# Pure_VCO_SMD_V2_2_d4f9a5cf-5e05-4fe2-98c.net
KiCad netlist of a schematic drawn in EAGLE
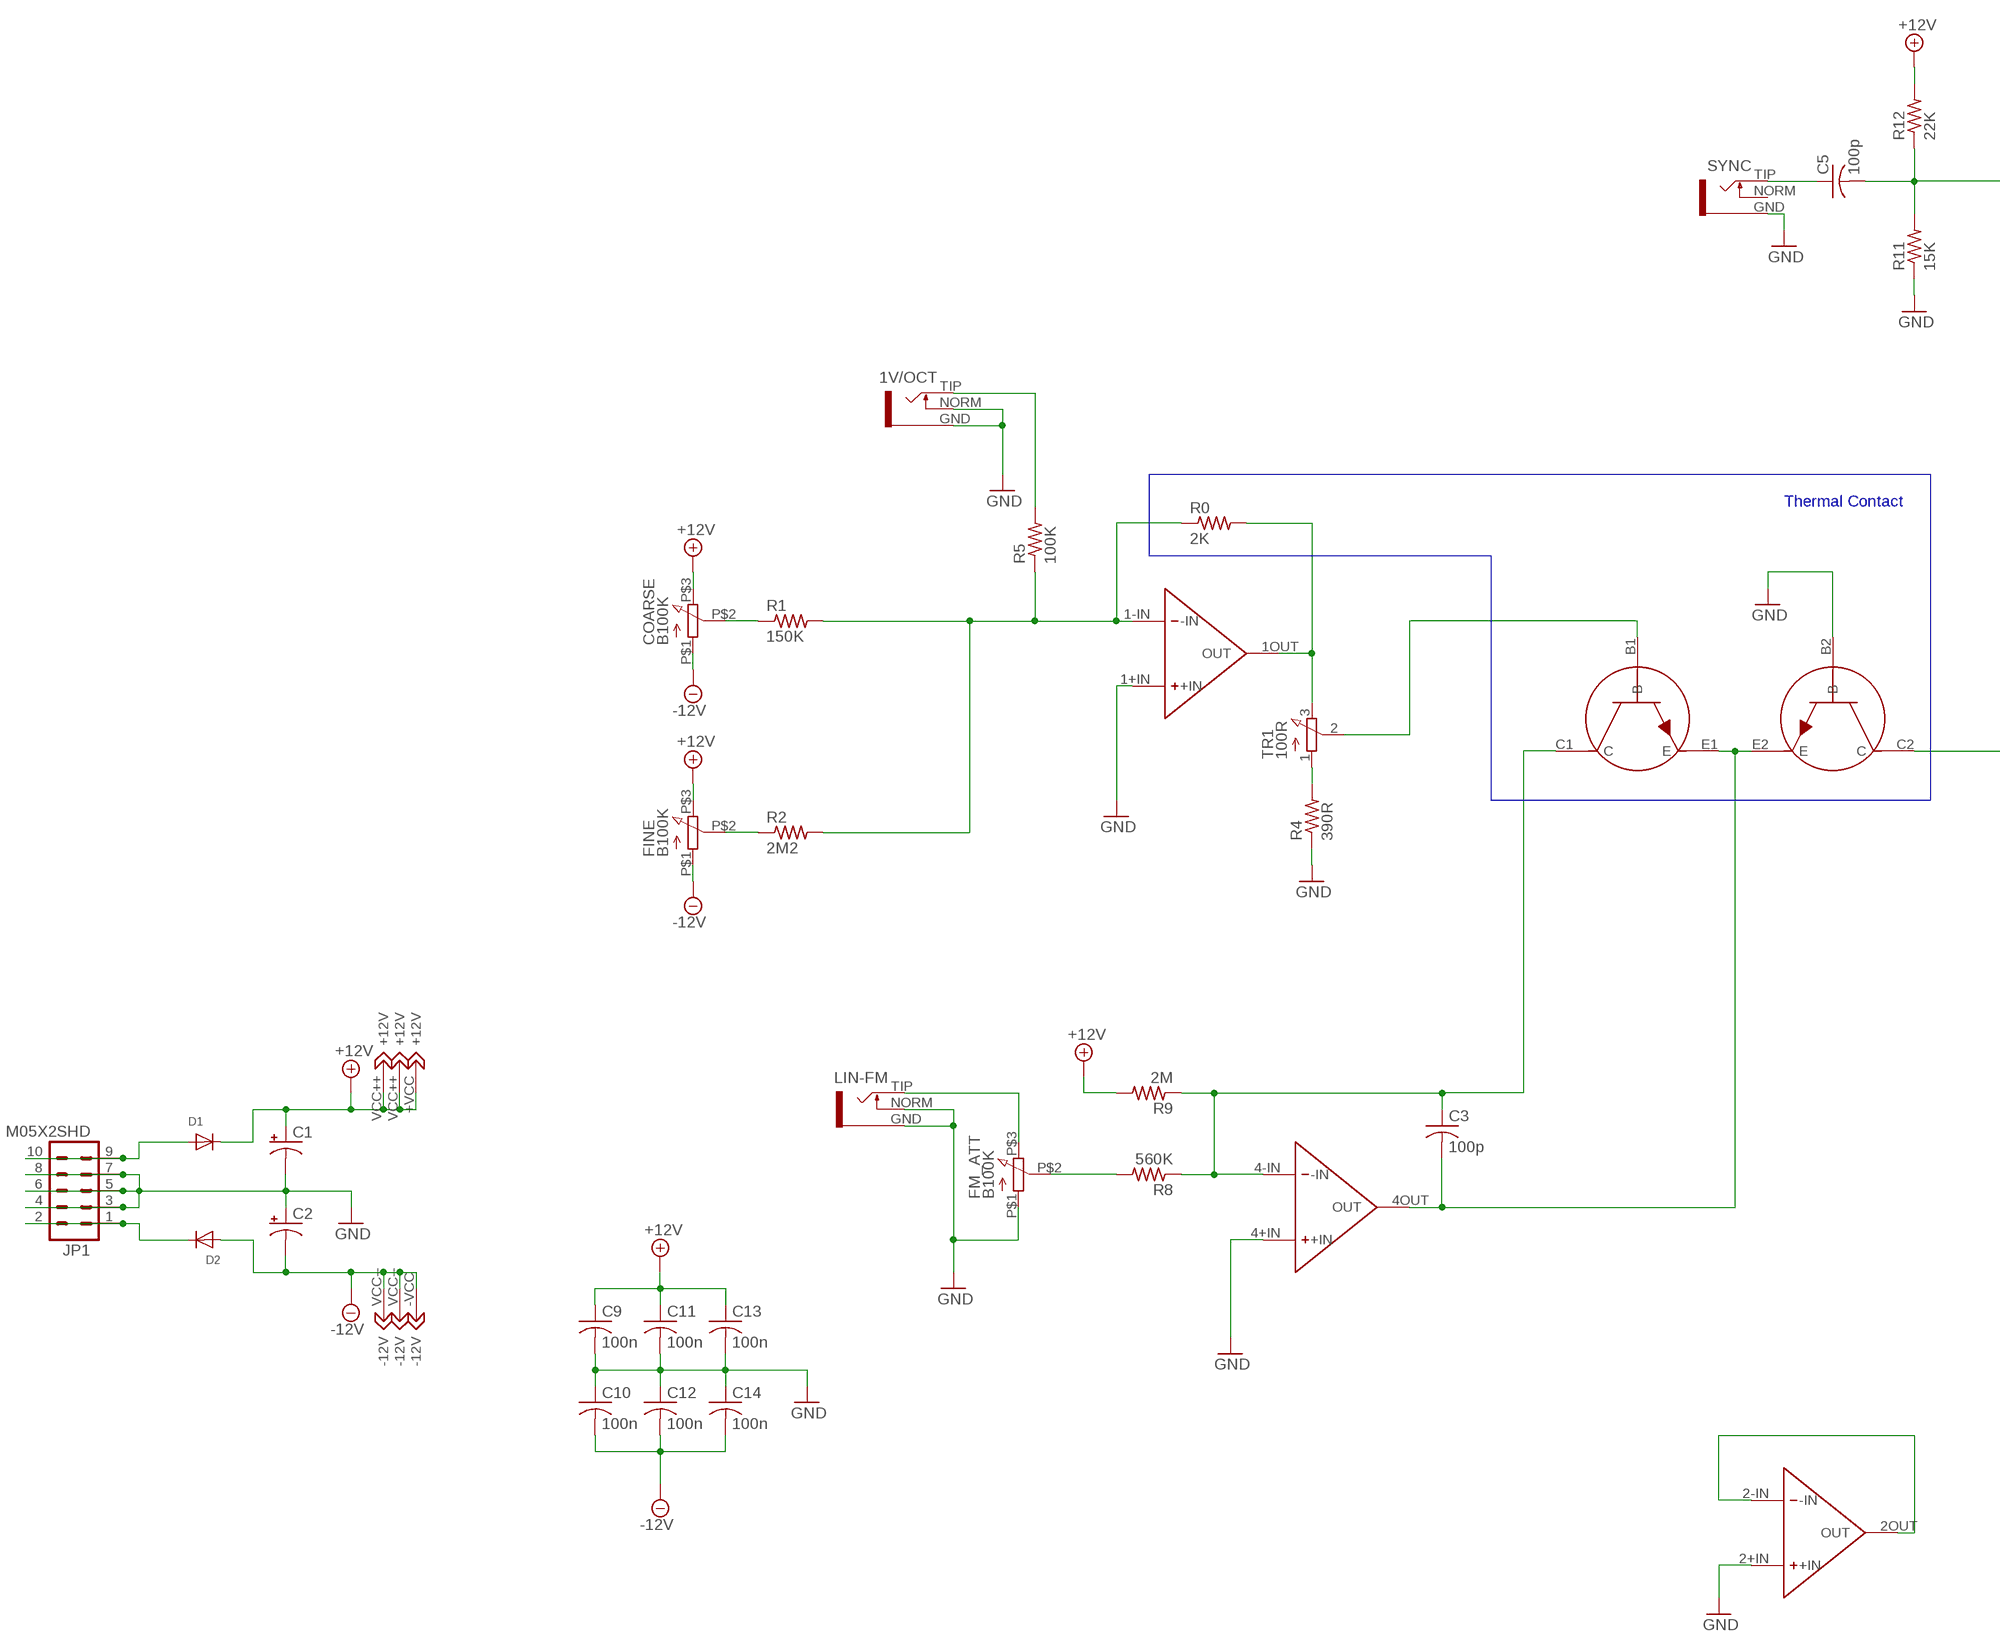
[diagram p0: schematic, sheet 1, part 1 of 2]
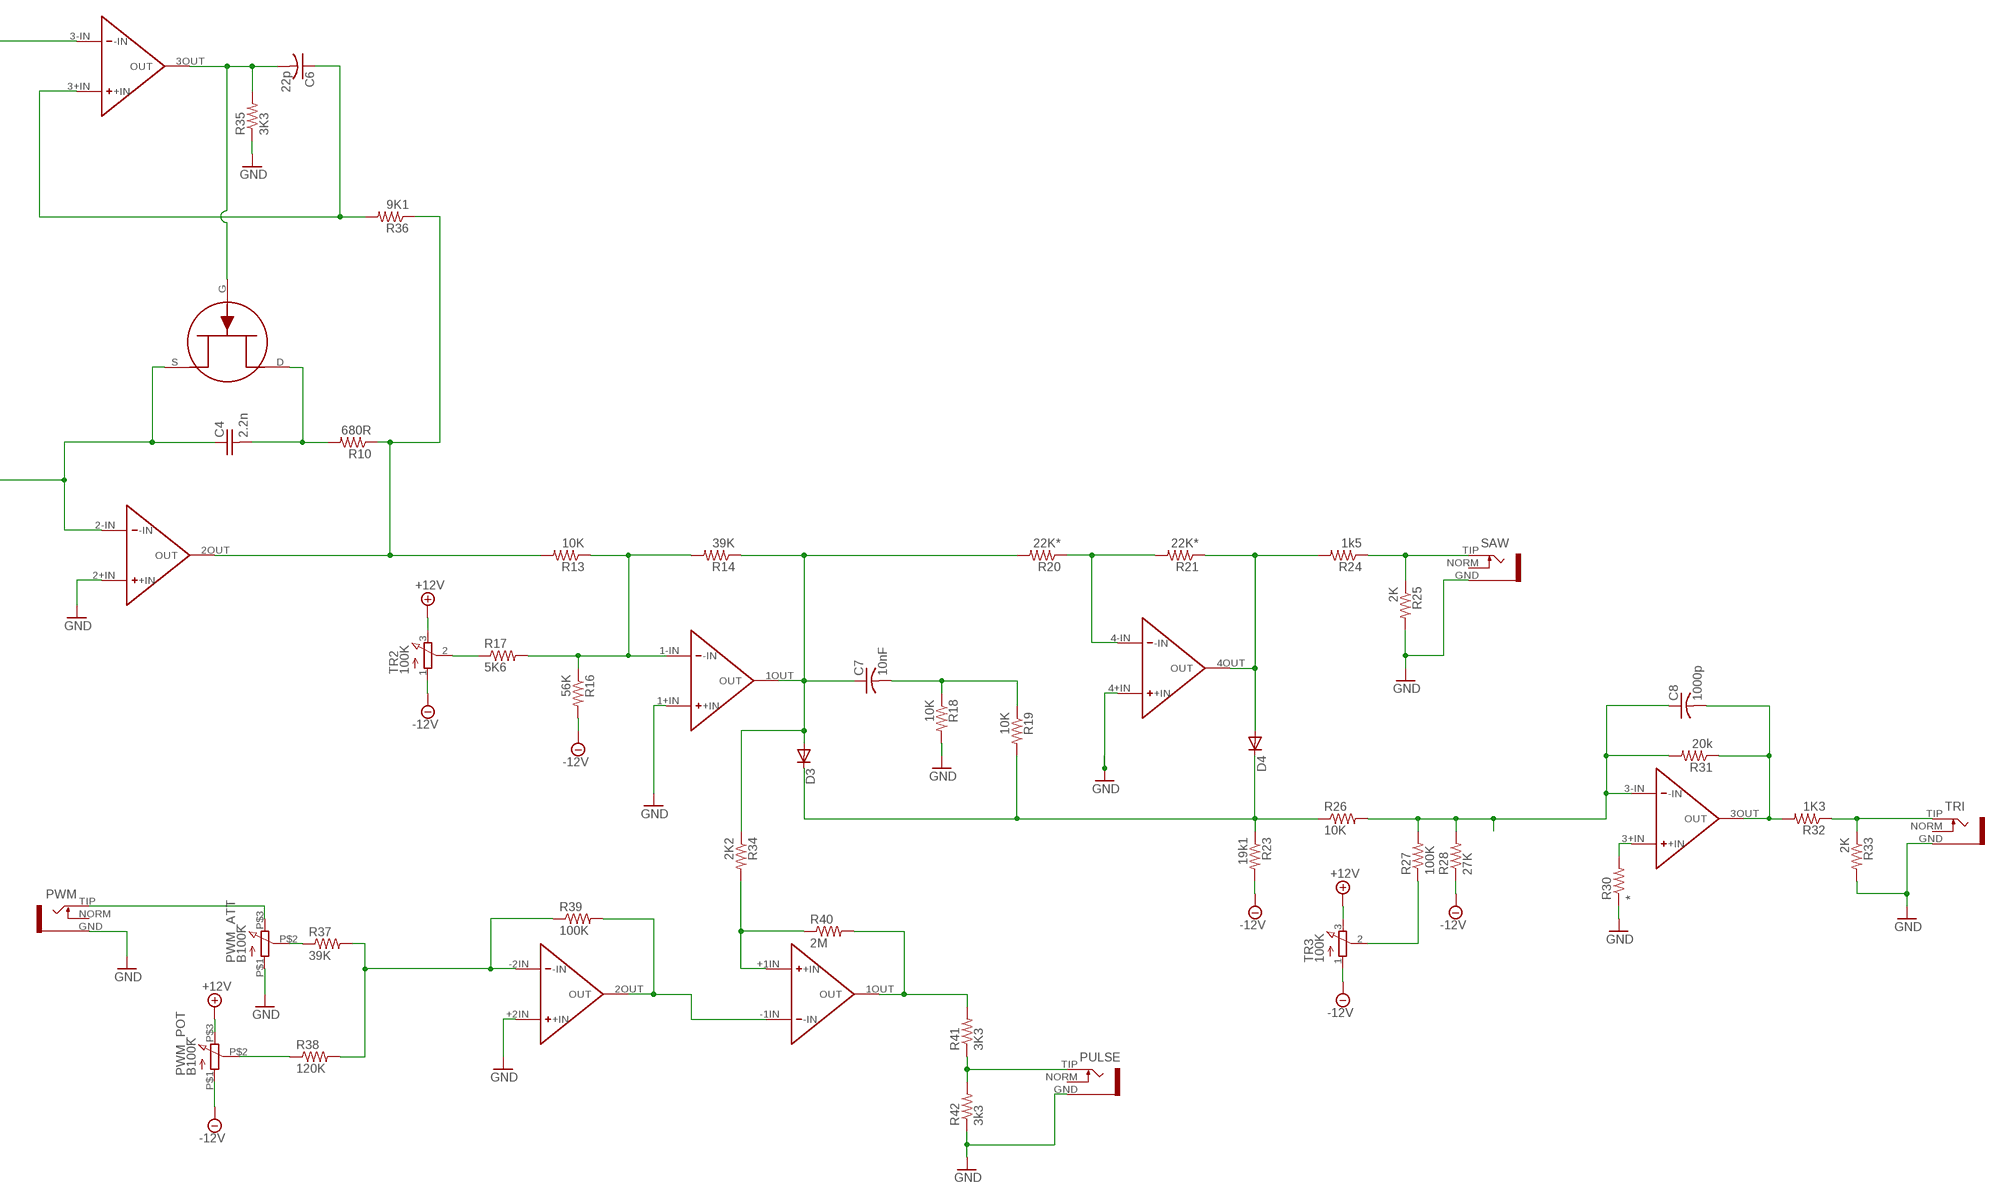
[diagram p1: schematic, sheet 1, part 2 of 2]

(export (version "E")
  (design (tool "Eeschema 10.0.6"))
  (components
    (comp (ref "1V/OCT")
      (value "S_JACK")
      (footprint "eagle-import:S_JACK")
      (libsource (lib "eagle-import") (part "S_JACK"))
    )
    (comp (ref "C1")
      (value "CPOL-US153CLV-0505")
      (footprint "eagle-import:153CLV-0505")
      (libsource (lib "eagle-import") (part "CPOL-US153CLV-0505"))
    )
    (comp (ref "C2")
      (value "CPOL-US153CLV-0505")
      (footprint "eagle-import:153CLV-0505")
      (libsource (lib "eagle-import") (part "CPOL-US153CLV-0505"))
    )
    (comp (ref "C3")
      (value "100p")
      (footprint "eagle-import:C0805K")
      (libsource (lib "eagle-import") (part "C-USC0805K"))
    )
    (comp (ref "C4")
      (value "2.2n")
      (footprint "eagle-import:POLY_CAP")
      (libsource (lib "eagle-import") (part "CAP_POLY"))
    )
    (comp (ref "C5")
      (value "100p")
      (footprint "eagle-import:C0805K")
      (libsource (lib "eagle-import") (part "C-USC0805K"))
    )
    (comp (ref "C6")
      (value "22p")
      (footprint "eagle-import:C0805K")
      (libsource (lib "eagle-import") (part "C-USC0805K"))
    )
    (comp (ref "C7")
      (value "10nF")
      (footprint "eagle-import:C0805K")
      (libsource (lib "eagle-import") (part "C-USC0805K"))
    )
    (comp (ref "C8")
      (value "1000p")
      (footprint "eagle-import:C0805K")
      (libsource (lib "eagle-import") (part "C-USC0805K"))
    )
    (comp (ref "C9")
      (value "100n")
      (footprint "eagle-import:C0805K")
      (libsource (lib "eagle-import") (part "C-USC0805K"))
    )
    (comp (ref "C10")
      (value "100n")
      (footprint "eagle-import:C0805K")
      (libsource (lib "eagle-import") (part "C-USC0805K"))
    )
    (comp (ref "C11")
      (value "100n")
      (footprint "eagle-import:C0805K")
      (libsource (lib "eagle-import") (part "C-USC0805K"))
    )
    (comp (ref "C12")
      (value "100n")
      (footprint "eagle-import:C0805K")
      (libsource (lib "eagle-import") (part "C-USC0805K"))
    )
    (comp (ref "C13")
      (value "100n")
      (footprint "eagle-import:C0805K")
      (libsource (lib "eagle-import") (part "C-USC0805K"))
    )
    (comp (ref "C14")
      (value "100n")
      (footprint "eagle-import:C0805K")
      (libsource (lib "eagle-import") (part "C-USC0805K"))
    )
    (comp (ref "COARSE")
      (value "B100K")
      (footprint "eagle-import:Q-POT")
      (libsource (lib "eagle-import") (part "Q-POT"))
    )
    (comp (ref "D1")
      (value "DIODESMA")
      (footprint "eagle-import:SMADIODE")
      (libsource (lib "eagle-import") (part "adafruit_DIODESMA"))
    )
    (comp (ref "D2")
      (value "DIODESMA")
      (footprint "eagle-import:SMADIODE")
      (libsource (lib "eagle-import") (part "adafruit_DIODESMA"))
    )
    (comp (ref "D3")
      (value "DIODESOD")
      (footprint "eagle-import:SOD-323")
      (libsource (lib "eagle-import") (part "DIODESOD"))
    )
    (comp (ref "D4")
      (value "DIODESOD")
      (footprint "eagle-import:SOD-323")
      (libsource (lib "eagle-import") (part "DIODESOD"))
    )
    (comp (ref "FINE")
      (value "B100K")
      (footprint "eagle-import:Q-POT")
      (libsource (lib "eagle-import") (part "Q-POT"))
    )
    (comp (ref "FM_ATT")
      (value "B100K")
      (footprint "eagle-import:Q-POT")
      (libsource (lib "eagle-import") (part "Q-POT"))
    )
    (comp (ref "JP1")
      (value "M05X2SHD")
      (footprint "eagle-import:2X5-SHROUDED")
      (libsource (lib "eagle-import") (part "M05X2SHD"))
    )
    (comp (ref "LIN-FM")
      (value "S_JACK")
      (footprint "eagle-import:S_JACK")
      (libsource (lib "eagle-import") (part "S_JACK"))
    )
    (comp (ref "PULSE")
      (value "S_JACK")
      (footprint "eagle-import:S_JACK")
      (libsource (lib "eagle-import") (part "S_JACK"))
    )
    (comp (ref "PWM")
      (value "S_JACK")
      (footprint "eagle-import:S_JACK")
      (libsource (lib "eagle-import") (part "S_JACK"))
    )
    (comp (ref "PWM_ATT")
      (value "B100K")
      (footprint "eagle-import:Q-POT")
      (libsource (lib "eagle-import") (part "Q-POT"))
    )
    (comp (ref "PWM_POT")
      (value "B100K")
      (footprint "eagle-import:Q-POT")
      (libsource (lib "eagle-import") (part "Q-POT"))
    )
    (comp (ref "R0")
      (value "2K")
      (footprint "eagle-import:RESISTOR_TC")
      (libsource (lib "eagle-import") (part "R_TC"))
    )
    (comp (ref "R1")
      (value "150K")
      (footprint "eagle-import:R0805")
      (libsource (lib "eagle-import") (part "R-US_R0805"))
    )
    (comp (ref "R2")
      (value "2M2")
      (footprint "eagle-import:R0805")
      (libsource (lib "eagle-import") (part "R-US_R0805"))
    )
    (comp (ref "R4")
      (value "390R")
      (footprint "eagle-import:R0805")
      (libsource (lib "eagle-import") (part "R-US_R0805"))
    )
    (comp (ref "R5")
      (value "100K")
      (footprint "eagle-import:R0805")
      (libsource (lib "eagle-import") (part "R-US_R0805"))
    )
    (comp (ref "R8")
      (value "560K")
      (footprint "eagle-import:R0805")
      (libsource (lib "eagle-import") (part "R-US_R0805"))
    )
    (comp (ref "R9")
      (value "2M")
      (footprint "eagle-import:R0805")
      (libsource (lib "eagle-import") (part "R-US_R0805"))
    )
    (comp (ref "R10")
      (value "680R")
      (footprint "eagle-import:R0805")
      (libsource (lib "eagle-import") (part "R-US_R0805"))
    )
    (comp (ref "R11")
      (value "15K")
      (footprint "eagle-import:R0805")
      (libsource (lib "eagle-import") (part "R-US_R0805"))
    )
    (comp (ref "R12")
      (value "22K")
      (footprint "eagle-import:R0805")
      (libsource (lib "eagle-import") (part "R-US_R0805"))
    )
    (comp (ref "R13")
      (value "10K")
      (footprint "eagle-import:R0805")
      (libsource (lib "eagle-import") (part "R-US_R0805"))
    )
    (comp (ref "R14")
      (value "39K")
      (footprint "eagle-import:R0805")
      (libsource (lib "eagle-import") (part "R-US_R0805"))
    )
    (comp (ref "R16")
      (value "56K")
      (footprint "eagle-import:R0805")
      (libsource (lib "eagle-import") (part "R-US_R0805"))
    )
    (comp (ref "R17")
      (value "5K6")
      (footprint "eagle-import:R0805")
      (libsource (lib "eagle-import") (part "R-US_R0805"))
    )
    (comp (ref "R18")
      (value "10K")
      (footprint "eagle-import:R0805")
      (libsource (lib "eagle-import") (part "R-US_R0805"))
    )
    (comp (ref "R19")
      (value "10K")
      (footprint "eagle-import:R0805")
      (libsource (lib "eagle-import") (part "R-US_R0805"))
    )
    (comp (ref "R20")
      (value "22K*")
      (footprint "eagle-import:R0805")
      (libsource (lib "eagle-import") (part "R-US_R0805"))
    )
    (comp (ref "R21")
      (value "22K*")
      (footprint "eagle-import:R0805")
      (libsource (lib "eagle-import") (part "R-US_R0805"))
    )
    (comp (ref "R23")
      (value "19k1")
      (footprint "eagle-import:R0805")
      (libsource (lib "eagle-import") (part "R-US_R0805"))
    )
    (comp (ref "R24")
      (value "1k5")
      (footprint "eagle-import:R0805")
      (libsource (lib "eagle-import") (part "R-US_R0805"))
    )
    (comp (ref "R25")
      (value "2K")
      (footprint "eagle-import:R0805")
      (libsource (lib "eagle-import") (part "R-US_R0805"))
    )
    (comp (ref "R26")
      (value "10K")
      (footprint "eagle-import:R0805")
      (libsource (lib "eagle-import") (part "R-US_R0805"))
    )
    (comp (ref "R27")
      (value "100K")
      (footprint "eagle-import:R0805")
      (libsource (lib "eagle-import") (part "R-US_R0805"))
    )
    (comp (ref "R28")
      (value "27K")
      (footprint "eagle-import:R0805")
      (libsource (lib "eagle-import") (part "R-US_R0805"))
    )
    (comp (ref "R30")
      (value "*")
      (footprint "eagle-import:R0805")
      (libsource (lib "eagle-import") (part "R-US_R0805"))
    )
    (comp (ref "R31")
      (value "20k")
      (footprint "eagle-import:R0805")
      (libsource (lib "eagle-import") (part "R-US_R0805"))
    )
    (comp (ref "R32")
      (value "1K3")
      (footprint "eagle-import:R0805")
      (libsource (lib "eagle-import") (part "R-US_R0805"))
    )
    (comp (ref "R33")
      (value "2K")
      (footprint "eagle-import:R0805")
      (libsource (lib "eagle-import") (part "R-US_R0805"))
    )
    (comp (ref "R34")
      (value "2K2")
      (footprint "eagle-import:R0805")
      (libsource (lib "eagle-import") (part "R-US_R0805"))
    )
    (comp (ref "R35")
      (value "3K3")
      (footprint "eagle-import:R0805")
      (libsource (lib "eagle-import") (part "R-US_R0805"))
    )
    (comp (ref "R36")
      (value "9K1")
      (footprint "eagle-import:R0805")
      (libsource (lib "eagle-import") (part "R-US_R0805"))
    )
    (comp (ref "R37")
      (value "39K")
      (footprint "eagle-import:R0805")
      (libsource (lib "eagle-import") (part "R-US_R0805"))
    )
    (comp (ref "R38")
      (value "120K")
      (footprint "eagle-import:R0805")
      (libsource (lib "eagle-import") (part "R-US_R0805"))
    )
    (comp (ref "R39")
      (value "100K")
      (footprint "eagle-import:R0805")
      (libsource (lib "eagle-import") (part "R-US_R0805"))
    )
    (comp (ref "R40")
      (value "2M")
      (footprint "eagle-import:R0805")
      (libsource (lib "eagle-import") (part "R-US_R0805"))
    )
    (comp (ref "R41")
      (value "3K3")
      (footprint "eagle-import:R0805")
      (libsource (lib "eagle-import") (part "R-US_R0805"))
    )
    (comp (ref "R42")
      (value "3k3")
      (footprint "eagle-import:R0805")
      (libsource (lib "eagle-import") (part "R-US_R0805"))
    )
    (comp (ref "SAW")
      (value "S_JACK")
      (footprint "eagle-import:S_JACK")
      (libsource (lib "eagle-import") (part "S_JACK"))
    )
    (comp (ref "SYNC")
      (value "S_JACK")
      (footprint "eagle-import:S_JACK")
      (libsource (lib "eagle-import") (part "S_JACK"))
    )
    (comp (ref "T1")
      (value "TRANS_PAIR")
      (footprint "eagle-import:TRANS_PAIR")
      (libsource (lib "eagle-import") (part "TRANS_PAIR"))
    )
    (comp (ref "T2")
      (value "N_CHN")
      (footprint "eagle-import:N_CHN")
      (libsource (lib "eagle-import") (part "N_CHN"))
    )
    (comp (ref "TR1")
      (value "100R")
      (footprint "eagle-import:TRIMMER_TH3")
      (libsource (lib "eagle-import") (part "TRIMMER_TH3"))
    )
    (comp (ref "TR2")
      (value "100K")
      (footprint "eagle-import:TRIM_3269W")
      (libsource (lib "eagle-import") (part "TRIM_3269W"))
    )
    (comp (ref "TR3")
      (value "100K")
      (footprint "eagle-import:TRIM_3269W")
      (libsource (lib "eagle-import") (part "TRIM_3269W"))
    )
    (comp (ref "TRI")
      (value "S_JACK")
      (footprint "eagle-import:S_JACK")
      (libsource (lib "eagle-import") (part "S_JACK"))
    )
    (comp (ref "U1")
      (value "QUAD_OPAMP")
      (footprint "eagle-import:QUAD_OPAMP")
      (libsource (lib "eagle-import") (part "QUAD_OPAMP"))
    )
    (comp (ref "U2")
      (value "QUAD_OPAMP")
      (footprint "eagle-import:QUAD_OPAMP")
      (libsource (lib "eagle-import") (part "QUAD_OPAMP"))
    )
    (comp (ref "U3")
      (value "DUAL_OPAMP")
      (footprint "eagle-import:DUAL_OPAMP")
      (libsource (lib "eagle-import") (part "DUAL_OPAMP"))
    )
  )
  (nets
    (net (code "1") (name "+12V") (class "Default")
      (node (ref "C1") (pin "+") (pinfunction "+_+") (pintype "passive"))
      (node (ref "C11") (pin "1") (pinfunction "1_1") (pintype "passive"))
      (node (ref "C13") (pin "1") (pinfunction "1_1") (pintype "passive"))
      (node (ref "C9") (pin "1") (pinfunction "1_1") (pintype "passive"))
      (node (ref "COARSE") (pin "P$3") (pinfunction "3_P$3") (pintype "passive"))
      (node (ref "D1") (pin "C") (pinfunction "C_C") (pintype "passive"))
      (node (ref "FINE") (pin "P$3") (pinfunction "3_P$3") (pintype "passive"))
      (node (ref "PWM_POT") (pin "P$3") (pinfunction "3_P$3") (pintype "passive"))
      (node (ref "R12") (pin "2") (pinfunction "2_2") (pintype "passive"))
      (node (ref "R9") (pin "2") (pinfunction "2_2") (pintype "passive"))
      (node (ref "TR2") (pin "3") (pinfunction "3_3") (pintype "passive"))
      (node (ref "TR3") (pin "3") (pinfunction "3_3") (pintype "passive"))
      (node (ref "U1") (pin "VCC++") (pinfunction "+12V_VCC++") (pintype "bidirectional"))
      (node (ref "U2") (pin "VCC++") (pinfunction "+12V_VCC++") (pintype "bidirectional"))
      (node (ref "U3") (pin "+VCC") (pinfunction "+12V_+VCC") (pintype "bidirectional"))
    )
    (net (code "2") (name "-12V") (class "Default")
      (node (ref "C10") (pin "2") (pinfunction "2_2") (pintype "passive"))
      (node (ref "C12") (pin "2") (pinfunction "2_2") (pintype "passive"))
      (node (ref "C14") (pin "2") (pinfunction "2_2") (pintype "passive"))
      (node (ref "C2") (pin "-") (pinfunction "-_-") (pintype "passive"))
      (node (ref "COARSE") (pin "P$1") (pinfunction "1_P$1") (pintype "passive"))
      (node (ref "D2") (pin "A") (pinfunction "A_A") (pintype "passive"))
      (node (ref "FINE") (pin "P$1") (pinfunction "1_P$1") (pintype "passive"))
      (node (ref "PWM_POT") (pin "P$1") (pinfunction "1_P$1") (pintype "passive"))
      (node (ref "R16") (pin "2") (pinfunction "2_2") (pintype "passive"))
      (node (ref "R23") (pin "2") (pinfunction "2_2") (pintype "passive"))
      (node (ref "R28") (pin "1") (pinfunction "1_1") (pintype "passive"))
      (node (ref "TR2") (pin "1") (pinfunction "1_1") (pintype "passive"))
      (node (ref "TR3") (pin "1") (pinfunction "1_1") (pintype "passive"))
      (node (ref "U1") (pin "VCC--") (pinfunction "-12V_VCC--") (pintype "bidirectional"))
      (node (ref "U2") (pin "VCC--") (pinfunction "-12V_VCC--") (pintype "bidirectional"))
      (node (ref "U3") (pin "-VCC") (pinfunction "-12V_-VCC") (pintype "bidirectional"))
    )
    (net (code "3") (name "GND") (class "Default")
      (node (ref "1V/OCT") (pin "GND") (pinfunction "GND_GND") (pintype "passive"))
      (node (ref "1V/OCT") (pin "NORM") (pinfunction "NORM_NORM") (pintype "passive"))
      (node (ref "C1") (pin "-") (pinfunction "-_-") (pintype "passive"))
      (node (ref "C10") (pin "1") (pinfunction "1_1") (pintype "passive"))
      (node (ref "C11") (pin "2") (pinfunction "2_2") (pintype "passive"))
      (node (ref "C12") (pin "1") (pinfunction "1_1") (pintype "passive"))
      (node (ref "C13") (pin "2") (pinfunction "2_2") (pintype "passive"))
      (node (ref "C14") (pin "1") (pinfunction "1_1") (pintype "passive"))
      (node (ref "C2") (pin "+") (pinfunction "+_+") (pintype "passive"))
      (node (ref "C9") (pin "2") (pinfunction "2_2") (pintype "passive"))
      (node (ref "FM_ATT") (pin "P$1") (pinfunction "1_P$1") (pintype "passive"))
      (node (ref "JP1") (pin "3") (pinfunction "3_3") (pintype "passive"))
      (node (ref "JP1") (pin "4") (pinfunction "4_4") (pintype "passive"))
      (node (ref "JP1") (pin "5") (pinfunction "5_5") (pintype "passive"))
      (node (ref "JP1") (pin "6") (pinfunction "6_6") (pintype "passive"))
      (node (ref "JP1") (pin "7") (pinfunction "7_7") (pintype "passive"))
      (node (ref "JP1") (pin "8") (pinfunction "8_8") (pintype "passive"))
      (node (ref "LIN-FM") (pin "GND") (pinfunction "GND_GND") (pintype "passive"))
      (node (ref "LIN-FM") (pin "NORM") (pinfunction "NORM_NORM") (pintype "passive"))
      (node (ref "PULSE") (pin "GND") (pinfunction "GND_GND") (pintype "passive"))
      (node (ref "PWM") (pin "GND") (pinfunction "GND_GND") (pintype "passive"))
      (node (ref "PWM_ATT") (pin "P$1") (pinfunction "1_P$1") (pintype "passive"))
      (node (ref "R11") (pin "1") (pinfunction "1_1") (pintype "passive"))
      (node (ref "R18") (pin "2") (pinfunction "2_2") (pintype "passive"))
      (node (ref "R25") (pin "2") (pinfunction "2_2") (pintype "passive"))
      (node (ref "R30") (pin "1") (pinfunction "1_1") (pintype "passive"))
      (node (ref "R33") (pin "2") (pinfunction "2_2") (pintype "passive"))
      (node (ref "R35") (pin "1") (pinfunction "1_1") (pintype "passive"))
      (node (ref "R4") (pin "1") (pinfunction "1_1") (pintype "passive"))
      (node (ref "R42") (pin "1") (pinfunction "1_1") (pintype "passive"))
      (node (ref "SAW") (pin "GND") (pinfunction "GND_GND") (pintype "passive"))
      (node (ref "SYNC") (pin "GND") (pinfunction "GND_GND") (pintype "passive"))
      (node (ref "T1") (pin "B2") (pinfunction "B_B2") (pintype "bidirectional"))
      (node (ref "TRI") (pin "GND") (pinfunction "GND_GND") (pintype "passive"))
      (node (ref "U1") (pin "1+IN") (pinfunction "+IN_1+IN") (pintype "bidirectional"))
      (node (ref "U1") (pin "2+IN") (pinfunction "+IN_2+IN") (pintype "bidirectional"))
      (node (ref "U1") (pin "4+IN") (pinfunction "+IN_4+IN") (pintype "bidirectional"))
      (node (ref "U2") (pin "1+IN") (pinfunction "+IN_1+IN") (pintype "bidirectional"))
      (node (ref "U2") (pin "2+IN") (pinfunction "+IN_2+IN") (pintype "bidirectional"))
      (node (ref "U2") (pin "4+IN") (pinfunction "+IN_4+IN") (pintype "bidirectional"))
      (node (ref "U3") (pin "+2IN") (pinfunction "+IN_+2IN") (pintype "bidirectional"))
    )
    (net (code "4") (name "Net-(1V/OCT-PadTIP)") (class "Default")
      (node (ref "1V/OCT") (pin "TIP") (pinfunction "TIP_TIP") (pintype "passive"))
      (node (ref "R5") (pin "2") (pinfunction "2_2") (pintype "passive"))
    )
    (net (code "5") (name "Net-(C4-+)") (class "Default")
      (node (ref "C4") (pin "1") (pinfunction "+_1") (pintype "passive"))
      (node (ref "T1") (pin "C2") (pinfunction "C_C2") (pintype "bidirectional"))
      (node (ref "T2") (pin "S") (pinfunction "S_S") (pintype "bidirectional"))
      (node (ref "U1") (pin "2-IN") (pinfunction "-IN_2-IN") (pintype "bidirectional"))
    )
    (net (code "6") (name "Net-(C4--)") (class "Default")
      (node (ref "C4") (pin "2") (pinfunction "-_2") (pintype "passive"))
      (node (ref "R10") (pin "2") (pinfunction "2_2") (pintype "passive"))
      (node (ref "T2") (pin "D") (pinfunction "D_D") (pintype "bidirectional"))
    )
    (net (code "7") (name "Net-(C5-Pad1)") (class "Default")
      (node (ref "C5") (pin "1") (pinfunction "1_1") (pintype "passive"))
      (node (ref "SYNC") (pin "TIP") (pinfunction "TIP_TIP") (pintype "passive"))
    )
    (net (code "8") (name "Net-(C7-Pad2)") (class "Default")
      (node (ref "C7") (pin "2") (pinfunction "2_2") (pintype "passive"))
      (node (ref "R18") (pin "1") (pinfunction "1_1") (pintype "passive"))
      (node (ref "R19") (pin "1") (pinfunction "1_1") (pintype "passive"))
    )
    (net (code "9") (name "Net-(COARSE-2)") (class "Default")
      (node (ref "COARSE") (pin "P$2") (pinfunction "2_P$2") (pintype "passive"))
      (node (ref "R1") (pin "1") (pinfunction "1_1") (pintype "passive"))
    )
    (net (code "10") (name "Net-(D1-PadA)") (class "Default")
      (node (ref "D1") (pin "A") (pinfunction "A_A") (pintype "passive"))
      (node (ref "JP1") (pin "10") (pinfunction "10_10") (pintype "passive"))
      (node (ref "JP1") (pin "9") (pinfunction "9_9") (pintype "passive"))
    )
    (net (code "11") (name "Net-(D2-PadC)") (class "Default")
      (node (ref "D2") (pin "C") (pinfunction "C_C") (pintype "passive"))
      (node (ref "JP1") (pin "1") (pinfunction "1_1") (pintype "passive"))
      (node (ref "JP1") (pin "2") (pinfunction "2_2") (pintype "passive"))
    )
    (net (code "12") (name "Net-(D3-A)") (class "Default")
      (node (ref "C7") (pin "1") (pinfunction "1_1") (pintype "passive"))
      (node (ref "D3") (pin "2") (pinfunction "A_2") (pintype "passive"))
      (node (ref "R14") (pin "1") (pinfunction "1_1") (pintype "passive"))
      (node (ref "R20") (pin "2") (pinfunction "2_2") (pintype "passive"))
      (node (ref "R34") (pin "1") (pinfunction "1_1") (pintype "passive"))
      (node (ref "U2") (pin "1OUT") (pinfunction "OUT_1OUT") (pintype "bidirectional"))
    )
    (net (code "13") (name "Net-(D3-C)") (class "Default")
      (node (ref "D3") (pin "1") (pinfunction "C_1") (pintype "passive"))
      (node (ref "D4") (pin "1") (pinfunction "C_1") (pintype "passive"))
      (node (ref "R19") (pin "2") (pinfunction "2_2") (pintype "passive"))
      (node (ref "R23") (pin "1") (pinfunction "1_1") (pintype "passive"))
      (node (ref "R26") (pin "1") (pinfunction "1_1") (pintype "passive"))
    )
    (net (code "14") (name "Net-(D4-A)") (class "Default")
      (node (ref "D4") (pin "2") (pinfunction "A_2") (pintype "passive"))
      (node (ref "R21") (pin "1") (pinfunction "1_1") (pintype "passive"))
      (node (ref "R24") (pin "2") (pinfunction "2_2") (pintype "passive"))
      (node (ref "U2") (pin "4OUT") (pinfunction "OUT_4OUT") (pintype "bidirectional"))
    )
    (net (code "15") (name "Net-(FINE-2)") (class "Default")
      (node (ref "FINE") (pin "P$2") (pinfunction "2_P$2") (pintype "passive"))
      (node (ref "R2") (pin "1") (pinfunction "1_1") (pintype "passive"))
    )
    (net (code "16") (name "Net-(FM_ATT-2)") (class "Default")
      (node (ref "FM_ATT") (pin "P$2") (pinfunction "2_P$2") (pintype "passive"))
      (node (ref "R8") (pin "2") (pinfunction "2_2") (pintype "passive"))
    )
    (net (code "17") (name "Net-(FM_ATT-3)") (class "Default")
      (node (ref "FM_ATT") (pin "P$3") (pinfunction "3_P$3") (pintype "passive"))
      (node (ref "LIN-FM") (pin "TIP") (pinfunction "TIP_TIP") (pintype "passive"))
    )
    (net (code "18") (name "Net-(PULSE-PadTIP)") (class "Default")
      (node (ref "PULSE") (pin "TIP") (pinfunction "TIP_TIP") (pintype "passive"))
      (node (ref "R41") (pin "1") (pinfunction "1_1") (pintype "passive"))
      (node (ref "R42") (pin "2") (pinfunction "2_2") (pintype "passive"))
    )
    (net (code "19") (name "Net-(PWM_ATT-2)") (class "Default")
      (node (ref "PWM_ATT") (pin "P$2") (pinfunction "2_P$2") (pintype "passive"))
      (node (ref "R37") (pin "1") (pinfunction "1_1") (pintype "passive"))
    )
    (net (code "20") (name "Net-(PWM_ATT-3)") (class "Default")
      (node (ref "PWM") (pin "TIP") (pinfunction "TIP_TIP") (pintype "passive"))
      (node (ref "PWM_ATT") (pin "P$3") (pinfunction "3_P$3") (pintype "passive"))
    )
    (net (code "21") (name "Net-(PWM_POT-2)") (class "Default")
      (node (ref "PWM_POT") (pin "P$2") (pinfunction "2_P$2") (pintype "passive"))
      (node (ref "R38") (pin "1") (pinfunction "1_1") (pintype "passive"))
    )
    (net (code "22") (name "Net-(R4-Pad2)") (class "Default")
      (node (ref "R4") (pin "2") (pinfunction "2_2") (pintype "passive"))
      (node (ref "TR1") (pin "1") (pinfunction "1_1") (pintype "passive"))
    )
    (net (code "23") (name "Net-(R17-Pad1)") (class "Default")
      (node (ref "R17") (pin "1") (pinfunction "1_1") (pintype "passive"))
      (node (ref "TR2") (pin "2") (pinfunction "2_2") (pintype "passive"))
    )
    (net (code "24") (name "Net-(R24-Pad1)") (class "Default")
      (node (ref "R24") (pin "1") (pinfunction "1_1") (pintype "passive"))
      (node (ref "R25") (pin "1") (pinfunction "1_1") (pintype "passive"))
      (node (ref "SAW") (pin "TIP") (pinfunction "TIP_TIP") (pintype "passive"))
    )
    (net (code "25") (name "Net-(R27-Pad1)") (class "Default")
      (node (ref "R27") (pin "1") (pinfunction "1_1") (pintype "passive"))
      (node (ref "TR3") (pin "2") (pinfunction "2_2") (pintype "passive"))
    )
    (net (code "26") (name "Net-(R32-Pad1)") (class "Default")
      (node (ref "R32") (pin "1") (pinfunction "1_1") (pintype "passive"))
      (node (ref "R33") (pin "1") (pinfunction "1_1") (pintype "passive"))
      (node (ref "TRI") (pin "TIP") (pinfunction "TIP_TIP") (pintype "passive"))
    )
    (net (code "27") (name "Net-(T1A-B)") (class "Default")
      (node (ref "T1") (pin "B1") (pinfunction "B_B1") (pintype "bidirectional"))
      (node (ref "TR1") (pin "2") (pinfunction "2_2") (pintype "passive"))
    )
    (net (code "28") (name "Net-(T1A-C)") (class "Default")
      (node (ref "C3") (pin "1") (pinfunction "1_1") (pintype "passive"))
      (node (ref "R8") (pin "1") (pinfunction "1_1") (pintype "passive"))
      (node (ref "R9") (pin "1") (pinfunction "1_1") (pintype "passive"))
      (node (ref "T1") (pin "C1") (pinfunction "C_C1") (pintype "bidirectional"))
      (node (ref "U1") (pin "4-IN") (pinfunction "-IN_4-IN") (pintype "bidirectional"))
    )
    (net (code "29") (name "Net-(T1A-E)") (class "Default")
      (node (ref "C3") (pin "2") (pinfunction "2_2") (pintype "passive"))
      (node (ref "T1") (pin "E1") (pinfunction "E_E1") (pintype "bidirectional"))
      (node (ref "T1") (pin "E2") (pinfunction "E_E2") (pintype "bidirectional"))
      (node (ref "U1") (pin "4OUT") (pinfunction "OUT_4OUT") (pintype "bidirectional"))
    )
    (net (code "30") (name "Net-(U1A--IN)") (class "Default")
      (node (ref "R0") (pin "1") (pinfunction "1_1") (pintype "passive"))
      (node (ref "R1") (pin "2") (pinfunction "2_2") (pintype "passive"))
      (node (ref "R2") (pin "2") (pinfunction "2_2") (pintype "passive"))
      (node (ref "R5") (pin "1") (pinfunction "1_1") (pintype "passive"))
      (node (ref "U1") (pin "1-IN") (pinfunction "-IN_1-IN") (pintype "bidirectional"))
    )
    (net (code "31") (name "Net-(U1A-OUT)") (class "Default")
      (node (ref "R0") (pin "2") (pinfunction "2_2") (pintype "passive"))
      (node (ref "TR1") (pin "3") (pinfunction "3_3") (pintype "passive"))
      (node (ref "U1") (pin "1OUT") (pinfunction "OUT_1OUT") (pintype "bidirectional"))
    )
    (net (code "32") (name "Net-(U1B-OUT)") (class "Default")
      (node (ref "R10") (pin "1") (pinfunction "1_1") (pintype "passive"))
      (node (ref "R13") (pin "2") (pinfunction "2_2") (pintype "passive"))
      (node (ref "R36") (pin "1") (pinfunction "1_1") (pintype "passive"))
      (node (ref "U1") (pin "2OUT") (pinfunction "OUT_2OUT") (pintype "bidirectional"))
    )
    (net (code "33") (name "Net-(U1C-+IN)") (class "Default")
      (node (ref "C6") (pin "1") (pinfunction "1_1") (pintype "passive"))
      (node (ref "R36") (pin "2") (pinfunction "2_2") (pintype "passive"))
      (node (ref "U1") (pin "3+IN") (pinfunction "+IN_3+IN") (pintype "bidirectional"))
    )
    (net (code "34") (name "Net-(U1C--IN)") (class "Default")
      (node (ref "C5") (pin "2") (pinfunction "2_2") (pintype "passive"))
      (node (ref "R11") (pin "2") (pinfunction "2_2") (pintype "passive"))
      (node (ref "R12") (pin "1") (pinfunction "1_1") (pintype "passive"))
      (node (ref "U1") (pin "3-IN") (pinfunction "-IN_3-IN") (pintype "bidirectional"))
    )
    (net (code "35") (name "Net-(U1C-OUT)") (class "Default")
      (node (ref "C6") (pin "2") (pinfunction "2_2") (pintype "passive"))
      (node (ref "R35") (pin "2") (pinfunction "2_2") (pintype "passive"))
      (node (ref "T2") (pin "G") (pinfunction "G_G") (pintype "bidirectional"))
      (node (ref "U1") (pin "3OUT") (pinfunction "OUT_3OUT") (pintype "bidirectional"))
    )
    (net (code "36") (name "Net-(U2A--IN)") (class "Default")
      (node (ref "R13") (pin "1") (pinfunction "1_1") (pintype "passive"))
      (node (ref "R14") (pin "2") (pinfunction "2_2") (pintype "passive"))
      (node (ref "R16") (pin "1") (pinfunction "1_1") (pintype "passive"))
      (node (ref "R17") (pin "2") (pinfunction "2_2") (pintype "passive"))
      (node (ref "U2") (pin "1-IN") (pinfunction "-IN_1-IN") (pintype "bidirectional"))
    )
    (net (code "37") (name "Net-(U2B--IN)") (class "Default")
      (node (ref "U2") (pin "2-IN") (pinfunction "-IN_2-IN") (pintype "bidirectional"))
      (node (ref "U2") (pin "2OUT") (pinfunction "OUT_2OUT") (pintype "bidirectional"))
    )
    (net (code "38") (name "Net-(U2C-+IN)") (class "Default")
      (node (ref "R30") (pin "2") (pinfunction "2_2") (pintype "passive"))
      (node (ref "U2") (pin "3+IN") (pinfunction "+IN_3+IN") (pintype "bidirectional"))
    )
    (net (code "39") (name "Net-(U2C--IN)") (class "Default")
      (node (ref "C8") (pin "1") (pinfunction "1_1") (pintype "passive"))
      (node (ref "R26") (pin "2") (pinfunction "2_2") (pintype "passive"))
      (node (ref "R27") (pin "2") (pinfunction "2_2") (pintype "passive"))
      (node (ref "R28") (pin "2") (pinfunction "2_2") (pintype "passive"))
      (node (ref "R31") (pin "2") (pinfunction "2_2") (pintype "passive"))
      (node (ref "U2") (pin "3-IN") (pinfunction "-IN_3-IN") (pintype "bidirectional"))
    )
    (net (code "40") (name "Net-(U2C-OUT)") (class "Default")
      (node (ref "C8") (pin "2") (pinfunction "2_2") (pintype "passive"))
      (node (ref "R31") (pin "1") (pinfunction "1_1") (pintype "passive"))
      (node (ref "R32") (pin "2") (pinfunction "2_2") (pintype "passive"))
      (node (ref "U2") (pin "3OUT") (pinfunction "OUT_3OUT") (pintype "bidirectional"))
    )
    (net (code "41") (name "Net-(U2D--IN)") (class "Default")
      (node (ref "R20") (pin "1") (pinfunction "1_1") (pintype "passive"))
      (node (ref "R21") (pin "2") (pinfunction "2_2") (pintype "passive"))
      (node (ref "U2") (pin "4-IN") (pinfunction "-IN_4-IN") (pintype "bidirectional"))
    )
    (net (code "42") (name "Net-(U3A-+IN)") (class "Default")
      (node (ref "R34") (pin "2") (pinfunction "2_2") (pintype "passive"))
      (node (ref "R40") (pin "1") (pinfunction "1_1") (pintype "passive"))
      (node (ref "U3") (pin "+1IN") (pinfunction "+IN_+1IN") (pintype "bidirectional"))
    )
    (net (code "43") (name "Net-(U3A--IN)") (class "Default")
      (node (ref "R39") (pin "2") (pinfunction "2_2") (pintype "passive"))
      (node (ref "U3") (pin "-1IN") (pinfunction "-IN_-1IN") (pintype "bidirectional"))
      (node (ref "U3") (pin "2OUT") (pinfunction "OUT_2OUT") (pintype "bidirectional"))
    )
    (net (code "44") (name "Net-(U3A-OUT)") (class "Default")
      (node (ref "R40") (pin "2") (pinfunction "2_2") (pintype "passive"))
      (node (ref "R41") (pin "2") (pinfunction "2_2") (pintype "passive"))
      (node (ref "U3") (pin "1OUT") (pinfunction "OUT_1OUT") (pintype "bidirectional"))
    )
    (net (code "45") (name "Net-(U3B--IN)") (class "Default")
      (node (ref "R37") (pin "2") (pinfunction "2_2") (pintype "passive"))
      (node (ref "R38") (pin "2") (pinfunction "2_2") (pintype "passive"))
      (node (ref "R39") (pin "1") (pinfunction "1_1") (pintype "passive"))
      (node (ref "U3") (pin "-2IN") (pinfunction "-IN_-2IN") (pintype "bidirectional"))
    )
    (net (code "46") (name "unconnected-(PULSE-PadNORM)") (class "Default")
      (node (ref "PULSE") (pin "NORM") (pinfunction "NORM_NORM") (pintype "passive"))
    )
    (net (code "47") (name "unconnected-(PWM-PadNORM)") (class "Default")
      (node (ref "PWM") (pin "NORM") (pinfunction "NORM_NORM") (pintype "passive"))
    )
    (net (code "48") (name "unconnected-(SAW-PadNORM)") (class "Default")
      (node (ref "SAW") (pin "NORM") (pinfunction "NORM_NORM") (pintype "passive"))
    )
    (net (code "49") (name "unconnected-(SYNC-PadNORM)") (class "Default")
      (node (ref "SYNC") (pin "NORM") (pinfunction "NORM_NORM") (pintype "passive"))
    )
    (net (code "50") (name "unconnected-(TRI-PadNORM)") (class "Default")
      (node (ref "TRI") (pin "NORM") (pinfunction "NORM_NORM") (pintype "passive"))
    )
  )
)
